# diy_striplight.net
KiCad netlist of a schematic drawn in EAGLE
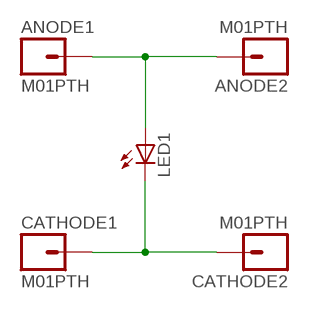
[diagram p0: schematic, sheet 1]

(export (version "E")
  (design (tool "Eeschema 10.0.6"))
  (components
    (comp (ref "ANODE1")
      (value "M01PTH")
      (footprint "eagle-import:1X01")
      (libsource (lib "eagle-import") (part "M01PTH"))
    )
    (comp (ref "ANODE2")
      (value "M01PTH")
      (footprint "eagle-import:1X01")
      (libsource (lib "eagle-import") (part "M01PTH"))
    )
    (comp (ref "CATHODE1")
      (value "M01PTH")
      (footprint "eagle-import:1X01")
      (libsource (lib "eagle-import") (part "M01PTH"))
    )
    (comp (ref "CATHODE2")
      (value "M01PTH")
      (footprint "eagle-import:1X01")
      (libsource (lib "eagle-import") (part "M01PTH"))
    )
    (comp (ref "LED1")
      (value "LEDCHIPLED_0603")
      (footprint "eagle-import:CHIPLED_0603")
      (libsource (lib "eagle-import") (part "LEDCHIPLED_0603"))
    )
  )
  (nets
    (net (code "1") (name "Net-(ANODE1-Pad1)") (class "Default")
      (node (ref "ANODE1") (pin "1") (pinfunction "1_1") (pintype "passive"))
      (node (ref "ANODE2") (pin "1") (pinfunction "1_1") (pintype "passive"))
      (node (ref "LED1") (pin "A") (pinfunction "A_A") (pintype "passive"))
    )
    (net (code "2") (name "Net-(CATHODE1-Pad1)") (class "Default")
      (node (ref "CATHODE1") (pin "1") (pinfunction "1_1") (pintype "passive"))
      (node (ref "CATHODE2") (pin "1") (pinfunction "1_1") (pintype "passive"))
      (node (ref "LED1") (pin "C") (pinfunction "C_C") (pintype "passive"))
    )
  )
)
